# main_board.net
KiCad netlist of a schematic drawn in EAGLE
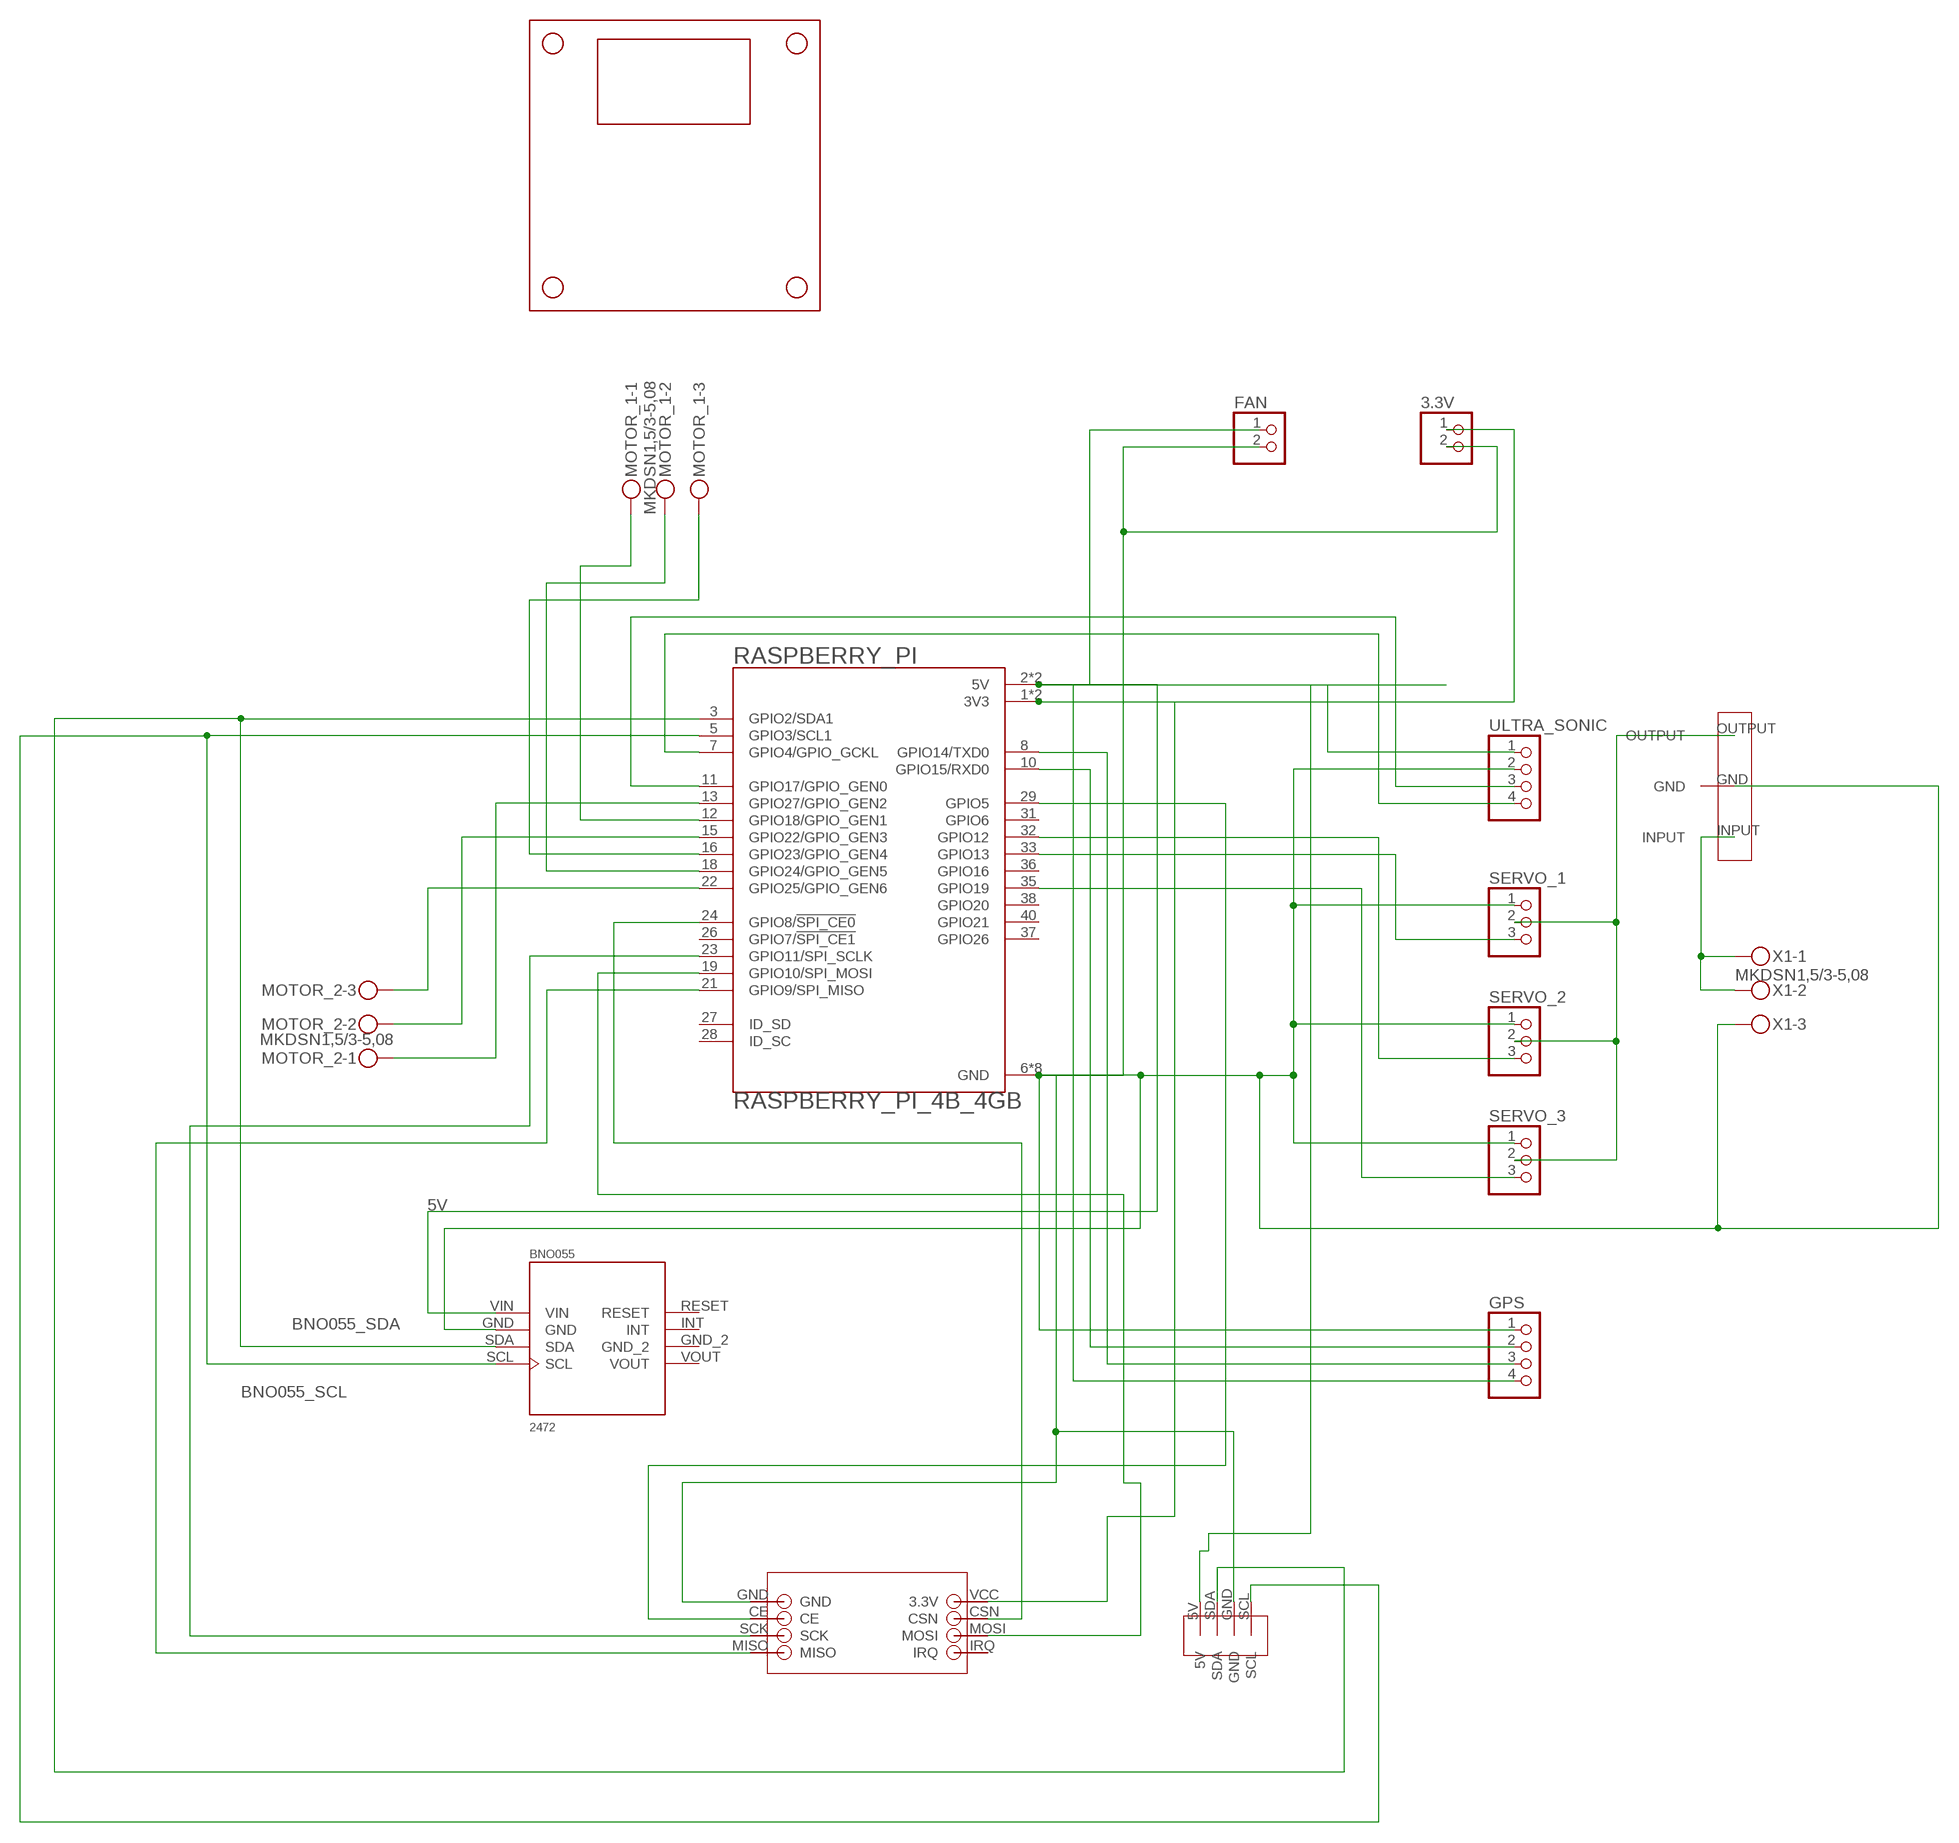
[diagram p0: schematic, sheet 1]

(export (version "E")
  (design (tool "Eeschema 10.0.6"))
  (components
    (comp (ref "3.3V")
      (value "PINHD-1X2")
      (footprint "eagle-import:1X02")
      (libsource (lib "eagle-import") (part "PINHD-1X2"))
    )
    (comp (ref "BNO055")
      (value "2472")
      (footprint "eagle-import:MODULE_2472")
      (fields (field (name "MF") "Adafruit"))
      (libsource (lib "eagle-import") (part "2472"))
    )
    (comp (ref "FAN")
      (value "PINHD-1X2")
      (footprint "eagle-import:1X02")
      (libsource (lib "eagle-import") (part "PINHD-1X2"))
    )
    (comp (ref "GPS")
      (value "PINHD-1X4")
      (footprint "eagle-import:1X04")
      (libsource (lib "eagle-import") (part "PINHD-1X4"))
    )
    (comp (ref "L298N1")
      (value "L298N_DRIVER")
      (footprint "eagle-import:L298N_DRIVER")
      (libsource (lib "eagle-import") (part "L298N_DRIVER"))
    )
    (comp (ref "LXDC1")
      (value "LXDC55")
      (footprint "eagle-import:LXDC55")
      (libsource (lib "eagle-import") (part "LXDC55"))
    )
    (comp (ref "MOTOR_1")
      (value "MKDSN1,5/3-5,08")
      (footprint "eagle-import:MKDSN1,5_3-5,08")
      (libsource (lib "eagle-import") (part "MKDSN1,5/3-5,08"))
    )
    (comp (ref "MOTOR_2")
      (value "MKDSN1,5/3-5,08")
      (footprint "eagle-import:MKDSN1,5_3-5,08")
      (libsource (lib "eagle-import") (part "MKDSN1,5/3-5,08"))
    )
    (comp (ref "NRF24L1")
      (value "NRF24L01")
      (footprint "eagle-import:NRF24L01")
      (libsource (lib "eagle-import") (part "NRF24L01"))
    )
    (comp (ref "RASPBERRY_PI")
      (value "RASPBERRY_PI_4B_4GB")
      (footprint "eagle-import:MODULE_RASPBERRY_PI_4B_4GB")
      (fields (field (name "MF") "Raspberry Pi") (field (name "MP") "RASPBERRY PI 4B/4GB"))
      (libsource (lib "eagle-import") (part "RASPBERRY_PI_4B_4GB"))
    )
    (comp (ref "SERVO_1")
      (value "PINHD-1X3")
      (footprint "eagle-import:1X03")
      (libsource (lib "eagle-import") (part "PINHD-1X3"))
    )
    (comp (ref "SERVO_2")
      (value "PINHD-1X3")
      (footprint "eagle-import:1X03")
      (libsource (lib "eagle-import") (part "PINHD-1X3"))
    )
    (comp (ref "SERVO_3")
      (value "PINHD-1X3")
      (footprint "eagle-import:1X03")
      (libsource (lib "eagle-import") (part "PINHD-1X3"))
    )
    (comp (ref "U$1")
      (value "DHT20")
      (footprint "eagle-import:DHT20")
      (libsource (lib "eagle-import") (part "DHT20"))
    )
    (comp (ref "ULTRA_SONIC")
      (value "PINHD-1X4")
      (footprint "eagle-import:1X04")
      (libsource (lib "eagle-import") (part "PINHD-1X4"))
    )
    (comp (ref "X1")
      (value "MKDSN1,5/3-5,08")
      (footprint "eagle-import:MKDSN1,5_3-5,08")
      (libsource (lib "eagle-import") (part "MKDSN1,5/3-5,08"))
    )
  )
  (nets
    (net (code "1") (name "/5V") (class "Default")
      (node (ref "BNO055") (pin "VIN") (pinfunction "VIN_VIN") (pintype "input"))
      (node (ref "FAN") (pin "1") (pinfunction "1_1") (pintype "passive"))
      (node (ref "GPS") (pin "4") (pinfunction "4_4") (pintype "passive"))
      (node (ref "RASPBERRY_PI") (pin "2") (pinfunction "5V_2") (pintype "power_in"))
      (node (ref "RASPBERRY_PI") (pin "4") (pinfunction "5V_4") (pintype "power_in"))
      (node (ref "U$1") (pin "5V") (pinfunction "5V_5V") (pintype "bidirectional"))
      (node (ref "ULTRA_SONIC") (pin "1") (pinfunction "1_1") (pintype "passive"))
    )
    (net (code "2") (name "/BNO055_SCL") (class "Default")
      (node (ref "BNO055") (pin "SCL") (pinfunction "SCL_SCL") (pintype "input"))
      (node (ref "RASPBERRY_PI") (pin "5") (pinfunction "GPIO3/SCL1_5") (pintype "bidirectional"))
      (node (ref "U$1") (pin "SCL") (pinfunction "SCL_SCL") (pintype "bidirectional"))
    )
    (net (code "3") (name "/BNO055_SDA") (class "Default")
      (node (ref "BNO055") (pin "SDA") (pinfunction "SDA_SDA") (pintype "bidirectional"))
      (node (ref "RASPBERRY_PI") (pin "3") (pinfunction "GPIO2/SDA1_3") (pintype "bidirectional"))
      (node (ref "U$1") (pin "SDA") (pinfunction "SDA_SDA") (pintype "bidirectional"))
    )
    (net (code "4") (name "Net-(LXDC1-PadOUTPUT)") (class "Default")
      (node (ref "LXDC1") (pin "OUTPUT") (pinfunction "OUTPUT_OUTPUT") (pintype "bidirectional"))
      (node (ref "SERVO_1") (pin "2") (pinfunction "2_2") (pintype "passive"))
      (node (ref "SERVO_2") (pin "2") (pinfunction "2_2") (pintype "passive"))
      (node (ref "SERVO_3") (pin "2") (pinfunction "2_2") (pintype "passive"))
    )
    (net (code "5") (name "Net-(MOTOR_1A-KL)") (class "Default")
      (node (ref "MOTOR_1") (pin "1") (pinfunction "KL_1") (pintype "passive"))
      (node (ref "RASPBERRY_PI") (pin "12") (pinfunction "GPIO18/GPIO_GEN1_12") (pintype "bidirectional"))
    )
    (net (code "6") (name "Net-(MOTOR_1B-KL)") (class "Default")
      (node (ref "MOTOR_1") (pin "2") (pinfunction "KL_2") (pintype "passive"))
      (node (ref "RASPBERRY_PI") (pin "18") (pinfunction "GPIO24/GPIO_GEN5_18") (pintype "bidirectional"))
    )
    (net (code "7") (name "Net-(MOTOR_1C-KL)") (class "Default")
      (node (ref "MOTOR_1") (pin "3") (pinfunction "KL_3") (pintype "passive"))
      (node (ref "RASPBERRY_PI") (pin "16") (pinfunction "GPIO23/GPIO_GEN4_16") (pintype "bidirectional"))
    )
    (net (code "8") (name "Net-(MOTOR_2A-KL)") (class "Default")
      (node (ref "MOTOR_2") (pin "1") (pinfunction "KL_1") (pintype "passive"))
      (node (ref "RASPBERRY_PI") (pin "13") (pinfunction "GPIO27/GPIO_GEN2_13") (pintype "bidirectional"))
    )
    (net (code "9") (name "Net-(MOTOR_2B-KL)") (class "Default")
      (node (ref "MOTOR_2") (pin "2") (pinfunction "KL_2") (pintype "passive"))
      (node (ref "RASPBERRY_PI") (pin "15") (pinfunction "GPIO22/GPIO_GEN3_15") (pintype "bidirectional"))
    )
    (net (code "10") (name "Net-(MOTOR_2C-KL)") (class "Default")
      (node (ref "MOTOR_2") (pin "3") (pinfunction "KL_3") (pintype "passive"))
      (node (ref "RASPBERRY_PI") (pin "22") (pinfunction "GPIO25/GPIO_GEN6_22") (pintype "bidirectional"))
    )
    (net (code "11") (name "Net-(NRF24L1-3.3V)") (class "Default")
      (node (ref "3.3V") (pin "1") (pinfunction "1_1") (pintype "passive"))
      (node (ref "NRF24L1") (pin "VCC") (pinfunction "3.3V_VCC") (pintype "bidirectional"))
      (node (ref "RASPBERRY_PI") (pin "1") (pinfunction "3V3_1") (pintype "power_in"))
      (node (ref "RASPBERRY_PI") (pin "17") (pinfunction "3V3_17") (pintype "power_in"))
    )
    (net (code "12") (name "Net-(RASPBERRY_PI-GPIO4{slash}GPIO_GCKL)") (class "Default")
      (node (ref "RASPBERRY_PI") (pin "7") (pinfunction "GPIO4/GPIO_GCKL_7") (pintype "bidirectional"))
      (node (ref "ULTRA_SONIC") (pin "4") (pinfunction "4_4") (pintype "passive"))
    )
    (net (code "13") (name "Net-(RASPBERRY_PI-GPIO5)") (class "Default")
      (node (ref "NRF24L1") (pin "CE") (pinfunction "CE_CE") (pintype "bidirectional"))
      (node (ref "RASPBERRY_PI") (pin "29") (pinfunction "GPIO5_29") (pintype "bidirectional"))
    )
    (net (code "14") (name "Net-(RASPBERRY_PI-GPIO8{slash}~{SPI_CE0})") (class "Default")
      (node (ref "NRF24L1") (pin "CSN") (pinfunction "CSN_CSN") (pintype "bidirectional"))
      (node (ref "RASPBERRY_PI") (pin "24") (pinfunction "GPIO8/~{SPI_CE0}_24") (pintype "bidirectional"))
    )
    (net (code "15") (name "Net-(RASPBERRY_PI-GPIO9{slash}SPI_MISO)") (class "Default")
      (node (ref "NRF24L1") (pin "MISO") (pinfunction "MISO_MISO") (pintype "bidirectional"))
      (node (ref "RASPBERRY_PI") (pin "21") (pinfunction "GPIO9/SPI_MISO_21") (pintype "bidirectional"))
    )
    (net (code "16") (name "Net-(RASPBERRY_PI-GPIO10{slash}SPI_MOSI)") (class "Default")
      (node (ref "NRF24L1") (pin "MOSI") (pinfunction "MOSI_MOSI") (pintype "bidirectional"))
      (node (ref "RASPBERRY_PI") (pin "19") (pinfunction "GPIO10/SPI_MOSI_19") (pintype "bidirectional"))
    )
    (net (code "17") (name "Net-(RASPBERRY_PI-GPIO11{slash}SPI_SCLK)") (class "Default")
      (node (ref "NRF24L1") (pin "SCK") (pinfunction "SCK_SCK") (pintype "bidirectional"))
      (node (ref "RASPBERRY_PI") (pin "23") (pinfunction "GPIO11/SPI_SCLK_23") (pintype "bidirectional"))
    )
    (net (code "18") (name "Net-(RASPBERRY_PI-GPIO12)") (class "Default")
      (node (ref "RASPBERRY_PI") (pin "32") (pinfunction "GPIO12_32") (pintype "bidirectional"))
      (node (ref "SERVO_2") (pin "3") (pinfunction "3_3") (pintype "passive"))
    )
    (net (code "19") (name "Net-(RASPBERRY_PI-GPIO13)") (class "Default")
      (node (ref "RASPBERRY_PI") (pin "33") (pinfunction "GPIO13_33") (pintype "bidirectional"))
      (node (ref "SERVO_1") (pin "3") (pinfunction "3_3") (pintype "passive"))
    )
    (net (code "20") (name "Net-(RASPBERRY_PI-GPIO14{slash}TXD0)") (class "Default")
      (node (ref "GPS") (pin "3") (pinfunction "3_3") (pintype "passive"))
      (node (ref "RASPBERRY_PI") (pin "8") (pinfunction "GPIO14/TXD0_8") (pintype "bidirectional"))
    )
    (net (code "21") (name "Net-(RASPBERRY_PI-GPIO15{slash}RXD0)") (class "Default")
      (node (ref "GPS") (pin "2") (pinfunction "2_2") (pintype "passive"))
      (node (ref "RASPBERRY_PI") (pin "10") (pinfunction "GPIO15/RXD0_10") (pintype "bidirectional"))
    )
    (net (code "22") (name "Net-(RASPBERRY_PI-GPIO17{slash}GPIO_GEN0)") (class "Default")
      (node (ref "RASPBERRY_PI") (pin "11") (pinfunction "GPIO17/GPIO_GEN0_11") (pintype "bidirectional"))
      (node (ref "ULTRA_SONIC") (pin "3") (pinfunction "3_3") (pintype "passive"))
    )
    (net (code "23") (name "Net-(RASPBERRY_PI-GPIO19)") (class "Default")
      (node (ref "RASPBERRY_PI") (pin "35") (pinfunction "GPIO19_35") (pintype "bidirectional"))
      (node (ref "SERVO_3") (pin "3") (pinfunction "3_3") (pintype "passive"))
    )
    (net (code "24") (name "Net-(X1A-KL)") (class "Default")
      (node (ref "LXDC1") (pin "INPUT") (pinfunction "INPUT_INPUT") (pintype "bidirectional"))
      (node (ref "X1") (pin "1") (pinfunction "KL_1") (pintype "passive"))
      (node (ref "X1") (pin "2") (pinfunction "KL_2") (pintype "passive"))
    )
    (net (code "25") (name "Net-(X1C-KL)") (class "Default")
      (node (ref "3.3V") (pin "2") (pinfunction "2_2") (pintype "passive"))
      (node (ref "BNO055") (pin "GND") (pinfunction "GND_GND") (pintype "input"))
      (node (ref "FAN") (pin "2") (pinfunction "2_2") (pintype "passive"))
      (node (ref "GPS") (pin "1") (pinfunction "1_1") (pintype "passive"))
      (node (ref "LXDC1") (pin "GND") (pinfunction "GND_GND") (pintype "bidirectional"))
      (node (ref "NRF24L1") (pin "GND") (pinfunction "GND_GND") (pintype "bidirectional"))
      (node (ref "RASPBERRY_PI") (pin "14") (pinfunction "GND_14") (pintype "power_in"))
      (node (ref "RASPBERRY_PI") (pin "20") (pinfunction "GND_20") (pintype "power_in"))
      (node (ref "RASPBERRY_PI") (pin "25") (pinfunction "GND_25") (pintype "power_in"))
      (node (ref "RASPBERRY_PI") (pin "30") (pinfunction "GND_30") (pintype "power_in"))
      (node (ref "RASPBERRY_PI") (pin "34") (pinfunction "GND_34") (pintype "power_in"))
      (node (ref "RASPBERRY_PI") (pin "39") (pinfunction "GND_39") (pintype "power_in"))
      (node (ref "RASPBERRY_PI") (pin "6") (pinfunction "GND_6") (pintype "power_in"))
      (node (ref "RASPBERRY_PI") (pin "9") (pinfunction "GND_9") (pintype "power_in"))
      (node (ref "SERVO_1") (pin "1") (pinfunction "1_1") (pintype "passive"))
      (node (ref "SERVO_2") (pin "1") (pinfunction "1_1") (pintype "passive"))
      (node (ref "SERVO_3") (pin "1") (pinfunction "1_1") (pintype "passive"))
      (node (ref "U$1") (pin "GND") (pinfunction "GND_GND") (pintype "bidirectional"))
      (node (ref "ULTRA_SONIC") (pin "2") (pinfunction "2_2") (pintype "passive"))
      (node (ref "X1") (pin "3") (pinfunction "KL_3") (pintype "passive"))
    )
    (net (code "26") (name "unconnected-(BNO055-PadGND_2)") (class "Default")
      (node (ref "BNO055") (pin "GND_2") (pinfunction "GND_2_GND_2") (pintype "output"))
    )
    (net (code "27") (name "unconnected-(BNO055-PadINT)") (class "Default")
      (node (ref "BNO055") (pin "INT") (pinfunction "INT_INT") (pintype "bidirectional"))
    )
    (net (code "28") (name "unconnected-(BNO055-PadRESET)") (class "Default")
      (node (ref "BNO055") (pin "RESET") (pinfunction "RESET_RESET") (pintype "bidirectional"))
    )
    (net (code "29") (name "unconnected-(BNO055-PadVOUT)") (class "Default")
      (node (ref "BNO055") (pin "VOUT") (pinfunction "VOUT_VOUT") (pintype "passive"))
    )
    (net (code "30") (name "unconnected-(NRF24L1-PadIRQ)") (class "Default")
      (node (ref "NRF24L1") (pin "IRQ") (pinfunction "IRQ_IRQ") (pintype "bidirectional"))
    )
    (net (code "31") (name "unconnected-(RASPBERRY_PI-GPIO6-Pad31)") (class "Default")
      (node (ref "RASPBERRY_PI") (pin "31") (pinfunction "GPIO6_31") (pintype "bidirectional"))
    )
    (net (code "32") (name "unconnected-(RASPBERRY_PI-GPIO7{slash}~{SPI_CE1}-Pad26)") (class "Default")
      (node (ref "RASPBERRY_PI") (pin "26") (pinfunction "GPIO7/~{SPI_CE1}_26") (pintype "bidirectional"))
    )
    (net (code "33") (name "unconnected-(RASPBERRY_PI-GPIO16-Pad36)") (class "Default")
      (node (ref "RASPBERRY_PI") (pin "36") (pinfunction "GPIO16_36") (pintype "bidirectional"))
    )
    (net (code "34") (name "unconnected-(RASPBERRY_PI-GPIO20-Pad38)") (class "Default")
      (node (ref "RASPBERRY_PI") (pin "38") (pinfunction "GPIO20_38") (pintype "bidirectional"))
    )
    (net (code "35") (name "unconnected-(RASPBERRY_PI-GPIO21-Pad40)") (class "Default")
      (node (ref "RASPBERRY_PI") (pin "40") (pinfunction "GPIO21_40") (pintype "bidirectional"))
    )
    (net (code "36") (name "unconnected-(RASPBERRY_PI-GPIO26-Pad37)") (class "Default")
      (node (ref "RASPBERRY_PI") (pin "37") (pinfunction "GPIO26_37") (pintype "bidirectional"))
    )
    (net (code "37") (name "unconnected-(RASPBERRY_PI-ID_SC-Pad28)") (class "Default")
      (node (ref "RASPBERRY_PI") (pin "28") (pinfunction "ID_SC_28") (pintype "bidirectional"))
    )
    (net (code "38") (name "unconnected-(RASPBERRY_PI-ID_SD-Pad27)") (class "Default")
      (node (ref "RASPBERRY_PI") (pin "27") (pinfunction "ID_SD_27") (pintype "bidirectional"))
    )
  )
)
